# ENCODERTESTINGSch.net
KiCad netlist of a schematic drawn in Altium Designer
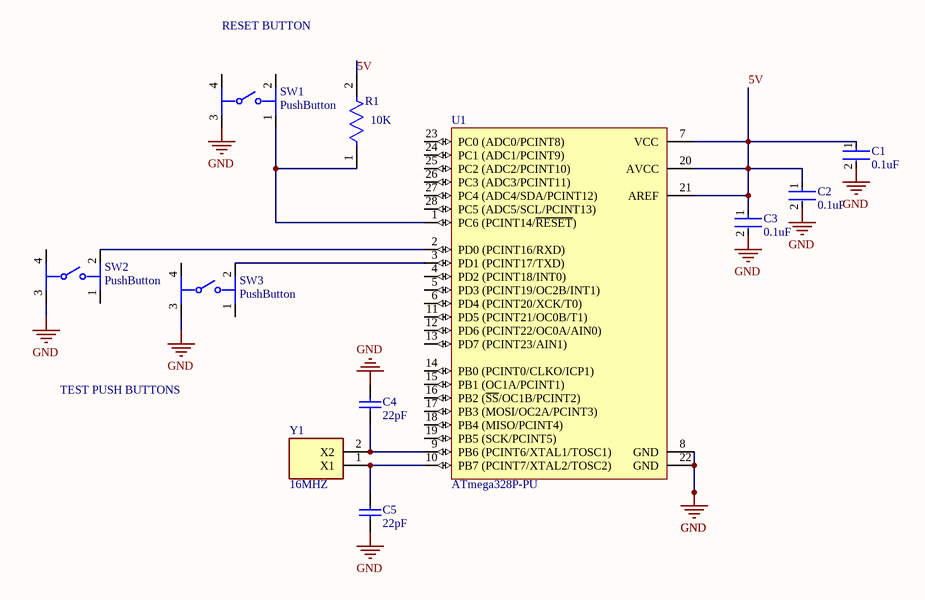
[diagram p0: ENCODERTESTINGSch.SchDoc]

(export (version "E")
  (design (tool "Eeschema 10.0.6"))
  (components
    (comp (ref "C1")
      (value "0.1uF")
      (footprint "FP-K15H5-MFG")
      (description "CAP CER 0.1UF 50V X7R RADIAL")
      (fields (field (name "VOLTAGE") "50V") (field (name "TOLERANCE") "10%"))
      (libsource (lib "Altium Content Vault") (part "11868f565c42a9108669ba33697ecf6"))
    )
    (comp (ref "C2")
      (value "0.1uF")
      (footprint "FP-K15H5-MFG")
      (description "CAP CER 0.1UF 50V X7R RADIAL")
      (fields (field (name "VOLTAGE") "50V") (field (name "TOLERANCE") "10%"))
      (libsource (lib "Altium Content Vault") (part "11868f565c42a9108669ba33697ecf6"))
    )
    (comp (ref "C3")
      (value "0.1uF")
      (footprint "FP-K15H5-MFG")
      (description "CAP CER 0.1UF 50V X7R RADIAL")
      (fields (field (name "VOLTAGE") "50V") (field (name "TOLERANCE") "10%"))
      (libsource (lib "Altium Content Vault") (part "11868f565c42a9108669ba33697ecf6"))
    )
    (comp (ref "C4")
      (value "22pF")
      (footprint "KEMT-C315-THT-2")
      (description "Capacitor, Ceramic, 22 pF, +/-10 %, 100 V, -55 to 125 degC, 2-Pin THD, RoHS, Bulk")
      (libsource (lib "Altium Content Vault") (part "CAP-NP-2"))
    )
    (comp (ref "C5")
      (value "22pF")
      (footprint "KEMT-C315-THT-2")
      (description "Capacitor, Ceramic, 22 pF, +/-10 %, 100 V, -55 to 125 degC, 2-Pin THD, RoHS, Bulk")
      (libsource (lib "Altium Content Vault") (part "CAP-NP-2"))
    )
    (comp (ref "R1")
      (value "10K")
      (footprint "FP-CRCW2512-e3-IPC_A")
      (description "RES Thick Film, 10kΩ, 5%, 1W, 200ppm/°C, 2512")
      (fields (field (name "TOLERANCE") "5%"))
      (libsource (lib "Altium Content Vault") (part "1029c3af85768c4190bb7ad29bc67b5"))
    )
    (comp (ref "SW1")
      (value "PushButton")
      (footprint "FP-FSM103-MFG")
      (description "SWITCH TACTILE SPST-NO 0.05A 24V")
      (libsource (lib "Altium Content Vault") (part "c0df99d12937e9d2da15afdedf14b17"))
    )
    (comp (ref "SW2")
      (value "PushButton")
      (footprint "FP-FSM103-MFG")
      (description "SWITCH TACTILE SPST-NO 0.05A 24V")
      (libsource (lib "Altium Content Vault") (part "c0df99d12937e9d2da15afdedf14b17"))
    )
    (comp (ref "SW3")
      (value "PushButton")
      (footprint "FP-FSM103-MFG")
      (description "SWITCH TACTILE SPST-NO 0.05A 24V")
      (libsource (lib "Altium Content Vault") (part "c0df99d12937e9d2da15afdedf14b17"))
    )
    (comp (ref "U1")
      (value "ATmega328P-PU")
      (footprint "28P3")
      (libsource (lib "Altium Content Vault") (part "MC-8B-ATM48-IL28"))
    )
    (comp (ref "Y1")
      (value "16MHZ")
      (footprint "SamacSys:ABL16000MHZB2")
      (description "Crystal or Oscillator")
      (fields
        (field (name "MANUFACTURER_PART_NUMBER") "ABL-16.000MHZ-B2")
        (field (name "MOUSER PART NUMBER") "815-ABL-16-B2")
      )
      (libsource (lib "*") (part "ABL-16.000MHZ-B2"))
    )
  )
  (nets
    (net (code "1") (name "/5V") (class "Default")
      (node (ref "C1") (pin "1") (pinfunction "1_1") (pintype "passive"))
      (node (ref "C2") (pin "1") (pinfunction "1_1") (pintype "passive"))
      (node (ref "C3") (pin "1") (pinfunction "1_1") (pintype "passive"))
      (node (ref "R1") (pin "2") (pinfunction "2_2") (pintype "passive"))
      (node (ref "U1") (pin "20") (pinfunction "AVCC_20") (pintype "power_in"))
      (node (ref "U1") (pin "21") (pinfunction "AREF_21") (pintype "power_in"))
      (node (ref "U1") (pin "7") (pinfunction "VCC_7") (pintype "power_in"))
    )
    (net (code "2") (name "GND") (class "Default")
      (node (ref "C1") (pin "2") (pinfunction "2_2") (pintype "passive"))
      (node (ref "C2") (pin "2") (pinfunction "2_2") (pintype "passive"))
      (node (ref "C3") (pin "2") (pinfunction "2_2") (pintype "passive"))
      (node (ref "C4") (pin "2") (pinfunction "2_2") (pintype "passive"))
      (node (ref "C5") (pin "1") (pinfunction "1_1") (pintype "passive"))
      (node (ref "SW1") (pin "3") (pinfunction "3_3") (pintype "passive"))
      (node (ref "SW2") (pin "3") (pinfunction "3_3") (pintype "passive"))
      (node (ref "SW3") (pin "3") (pinfunction "3_3") (pintype "passive"))
      (node (ref "U1") (pin "22") (pinfunction "GND_22") (pintype "power_in"))
      (node (ref "U1") (pin "8") (pinfunction "GND_8") (pintype "power_in"))
    )
    (net (code "3") (name "Net-(U1-PB6_(PCINT6{slash}XTAL1{slash}TOSC1))") (class "Default")
      (node (ref "C4") (pin "1") (pinfunction "1_1") (pintype "passive"))
      (node (ref "U1") (pin "9") (pinfunction "PB6_(PCINT6/XTAL1/TOSC1)_9") (pintype "bidirectional"))
      (node (ref "Y1") (pin "2") (pinfunction "X2_2") (pintype "passive"))
    )
    (net (code "4") (name "Net-(U1-PB7_(PCINT7{slash}XTAL2{slash}TOSC2))") (class "Default")
      (node (ref "C5") (pin "2") (pinfunction "2_2") (pintype "passive"))
      (node (ref "U1") (pin "10") (pinfunction "PB7_(PCINT7/XTAL2/TOSC2)_10") (pintype "bidirectional"))
      (node (ref "Y1") (pin "1") (pinfunction "X1_1") (pintype "passive"))
    )
    (net (code "5") (name "Net-(U1-PC6_(PCINT14{slash}~{RESET}))") (class "Default")
      (node (ref "R1") (pin "1") (pinfunction "1_1") (pintype "passive"))
      (node (ref "SW1") (pin "1") (pinfunction "1_1") (pintype "passive"))
      (node (ref "U1") (pin "1") (pinfunction "PC6_(PCINT14/~{RESET})_1") (pintype "bidirectional"))
    )
    (net (code "6") (name "Net-(U1-PD0_(PCINT16{slash}RXD))") (class "Default")
      (node (ref "SW2") (pin "2") (pinfunction "2_2") (pintype "passive"))
      (node (ref "U1") (pin "2") (pinfunction "PD0_(PCINT16/RXD)_2") (pintype "bidirectional"))
    )
    (net (code "7") (name "Net-(U1-PD1_(PCINT17{slash}TXD))") (class "Default")
      (node (ref "SW3") (pin "2") (pinfunction "2_2") (pintype "passive"))
      (node (ref "U1") (pin "3") (pinfunction "PD1_(PCINT17/TXD)_3") (pintype "bidirectional"))
    )
    (net (code "8") (name "unconnected-(SW1-Pad2)") (class "Default")
      (node (ref "SW1") (pin "2") (pinfunction "2_2") (pintype "passive"))
    )
    (net (code "9") (name "unconnected-(SW1-Pad4)") (class "Default")
      (node (ref "SW1") (pin "4") (pinfunction "4_4") (pintype "passive"))
    )
    (net (code "10") (name "unconnected-(SW2-Pad1)") (class "Default")
      (node (ref "SW2") (pin "1") (pinfunction "1_1") (pintype "passive"))
    )
    (net (code "11") (name "unconnected-(SW2-Pad4)") (class "Default")
      (node (ref "SW2") (pin "4") (pinfunction "4_4") (pintype "passive"))
    )
    (net (code "12") (name "unconnected-(SW3-Pad1)") (class "Default")
      (node (ref "SW3") (pin "1") (pinfunction "1_1") (pintype "passive"))
    )
    (net (code "13") (name "unconnected-(SW3-Pad4)") (class "Default")
      (node (ref "SW3") (pin "4") (pinfunction "4_4") (pintype "passive"))
    )
    (net (code "14") (name "unconnected-(U1-PB0_(PCINT0{slash}CLKO{slash}ICP1)-Pad14)") (class "Default")
      (node (ref "U1") (pin "14") (pinfunction "PB0_(PCINT0/CLKO/ICP1)_14") (pintype "bidirectional"))
    )
    (net (code "15") (name "unconnected-(U1-PB1_(OC1A{slash}PCINT1)-Pad15)") (class "Default")
      (node (ref "U1") (pin "15") (pinfunction "PB1_(OC1A/PCINT1)_15") (pintype "bidirectional"))
    )
    (net (code "16") (name "unconnected-(U1-PB2_(~{SS}{slash}OC1B{slash}PCINT2)-Pad16)") (class "Default")
      (node (ref "U1") (pin "16") (pinfunction "PB2_(~{SS}/OC1B/PCINT2)_16") (pintype "bidirectional"))
    )
    (net (code "17") (name "unconnected-(U1-PB3_(MOSI{slash}OC2A{slash}PCINT3)-Pad17)") (class "Default")
      (node (ref "U1") (pin "17") (pinfunction "PB3_(MOSI/OC2A/PCINT3)_17") (pintype "bidirectional"))
    )
    (net (code "18") (name "unconnected-(U1-PB4_(MISO{slash}PCINT4)-Pad18)") (class "Default")
      (node (ref "U1") (pin "18") (pinfunction "PB4_(MISO/PCINT4)_18") (pintype "bidirectional"))
    )
    (net (code "19") (name "unconnected-(U1-PB5_(SCK{slash}PCINT5)-Pad19)") (class "Default")
      (node (ref "U1") (pin "19") (pinfunction "PB5_(SCK/PCINT5)_19") (pintype "bidirectional"))
    )
    (net (code "20") (name "unconnected-(U1-PC0_(ADC0{slash}PCINT8)-Pad23)") (class "Default")
      (node (ref "U1") (pin "23") (pinfunction "PC0_(ADC0/PCINT8)_23") (pintype "bidirectional"))
    )
    (net (code "21") (name "unconnected-(U1-PC1_(ADC1{slash}PCINT9)-Pad24)") (class "Default")
      (node (ref "U1") (pin "24") (pinfunction "PC1_(ADC1/PCINT9)_24") (pintype "bidirectional"))
    )
    (net (code "22") (name "unconnected-(U1-PC2_(ADC2{slash}PCINT10)-Pad25)") (class "Default")
      (node (ref "U1") (pin "25") (pinfunction "PC2_(ADC2/PCINT10)_25") (pintype "bidirectional"))
    )
    (net (code "23") (name "unconnected-(U1-PC3_(ADC3{slash}PCINT11)-Pad26)") (class "Default")
      (node (ref "U1") (pin "26") (pinfunction "PC3_(ADC3/PCINT11)_26") (pintype "bidirectional"))
    )
    (net (code "24") (name "unconnected-(U1-PC4_(ADC4{slash}SDA{slash}PCINT12)-Pad27)") (class "Default")
      (node (ref "U1") (pin "27") (pinfunction "PC4_(ADC4/SDA/PCINT12)_27") (pintype "bidirectional"))
    )
    (net (code "25") (name "unconnected-(U1-PC5_(ADC5{slash}SCL{slash}PCINT13)-Pad28)") (class "Default")
      (node (ref "U1") (pin "28") (pinfunction "PC5_(ADC5/SCL/PCINT13)_28") (pintype "bidirectional"))
    )
    (net (code "26") (name "unconnected-(U1-PD2_(PCINT18{slash}INT0)-Pad4)") (class "Default")
      (node (ref "U1") (pin "4") (pinfunction "PD2_(PCINT18/INT0)_4") (pintype "bidirectional"))
    )
    (net (code "27") (name "unconnected-(U1-PD3_(PCINT19{slash}OC2B{slash}INT1)-Pad5)") (class "Default")
      (node (ref "U1") (pin "5") (pinfunction "PD3_(PCINT19/OC2B/INT1)_5") (pintype "bidirectional"))
    )
    (net (code "28") (name "unconnected-(U1-PD4_(PCINT20{slash}XCK{slash}T0)-Pad6)") (class "Default")
      (node (ref "U1") (pin "6") (pinfunction "PD4_(PCINT20/XCK/T0)_6") (pintype "bidirectional"))
    )
    (net (code "29") (name "unconnected-(U1-PD5_(PCINT21{slash}OC0B{slash}T1)-Pad11)") (class "Default")
      (node (ref "U1") (pin "11") (pinfunction "PD5_(PCINT21/OC0B/T1)_11") (pintype "bidirectional"))
    )
    (net (code "30") (name "unconnected-(U1-PD6_(PCINT22{slash}OC0A{slash}AIN0)-Pad12)") (class "Default")
      (node (ref "U1") (pin "12") (pinfunction "PD6_(PCINT22/OC0A/AIN0)_12") (pintype "bidirectional"))
    )
    (net (code "31") (name "unconnected-(U1-PD7_(PCINT23{slash}AIN1)-Pad13)") (class "Default")
      (node (ref "U1") (pin "13") (pinfunction "PD7_(PCINT23/AIN1)_13") (pintype "bidirectional"))
    )
  )
)
